# BQ51013BSCH.net
KiCad netlist of a schematic drawn in Altium Designer
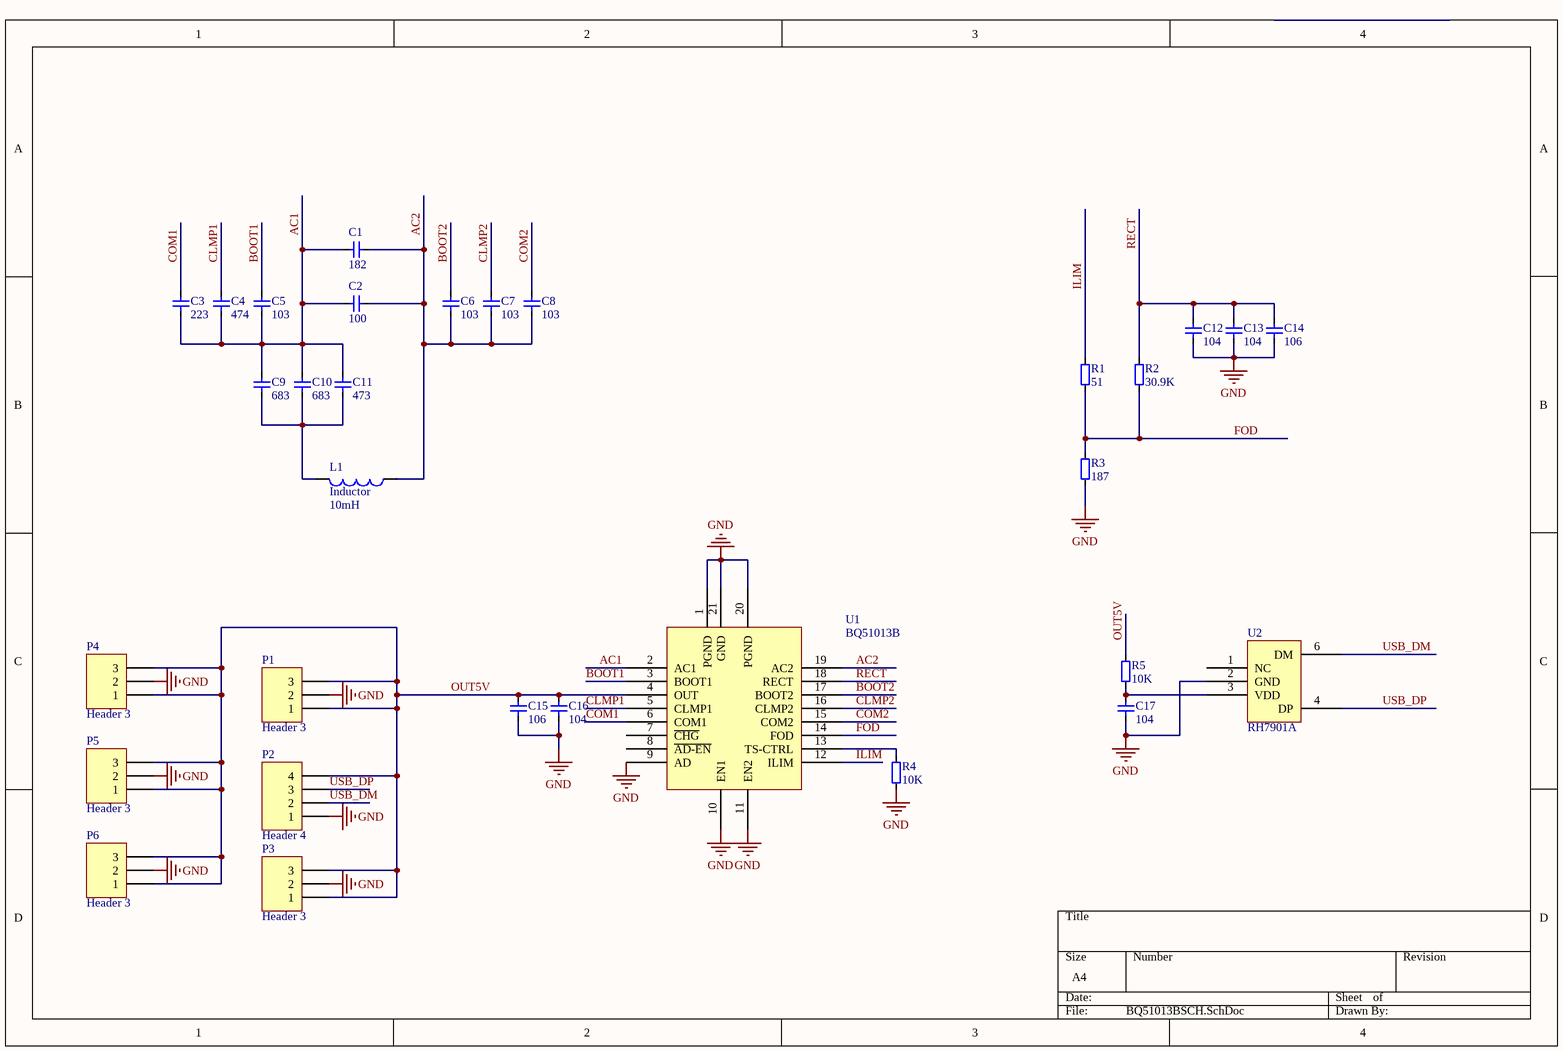
[diagram p0: BQ51013BSCH.SchDoc]

(export (version "E")
  (design (tool "Eeschema 10.0.6"))
  (components
    (comp (ref "C1")
      (value "182")
      (footprint "RECTANGLE/5.5/7.5/2.5")
      (description "Capacitor")
      (libsource (lib "5V1A1.1") (part "CAP1"))
    )
    (comp (ref "C2")
      (value "100")
      (footprint "RECTANGLE/5.5/7.5/2.5")
      (description "Capacitor")
      (libsource (lib "WP8AA0") (part "CAP1"))
    )
    (comp (ref "C3") (value "223") (description "Capacitor") (libsource (lib "5V1A1.1") (part "CAP1")))
    (comp (ref "C4")
      (value "474")
      (footprint "RECTANGLE/5.5/7.5/2.5")
      (description "Capacitor")
      (libsource (lib "5V1A1.1") (part "CAP1"))
    )
    (comp (ref "C5")
      (value "103")
      (footprint "RECTANGLE/5.5/7.5/2.5")
      (description "Capacitor")
      (libsource (lib "5V1A1.1") (part "CAP1"))
    )
    (comp (ref "C6")
      (value "103")
      (footprint "RECTANGLE/5.5/7.5/2.5")
      (description "Capacitor")
      (libsource (lib "5V1A1.1") (part "CAP1"))
    )
    (comp (ref "C7")
      (value "103")
      (footprint "RECTANGLE/5.5/7.5/2.5")
      (description "Capacitor")
      (libsource (lib "5V1A1.1") (part "CAP1"))
    )
    (comp (ref "C8")
      (value "103")
      (footprint "RECTANGLE/5.5/7.5/2.5")
      (description "Capacitor")
      (libsource (lib "5V1A1.1") (part "CAP1"))
    )
    (comp (ref "C9")
      (value "683")
      (footprint "RECTANGLE/5.5/7.5/2.5")
      (description "Capacitor")
      (libsource (lib "5V1A1.1") (part "CAP1"))
    )
    (comp (ref "C10")
      (value "683")
      (footprint "RECTANGLE/5.5/7.5/2.5")
      (description "Capacitor")
      (libsource (lib "5V1A1.1") (part "CAP1"))
    )
    (comp (ref "C11")
      (value "473")
      (footprint "RECTANGLE/5.5/7.5/2.5")
      (description "Capacitor")
      (libsource (lib "5V1A1.1") (part "CAP1"))
    )
    (comp (ref "C12")
      (value "104")
      (footprint "RECTANGLE/5.5/7.5/2.5")
      (description "Capacitor")
      (libsource (lib "5V1A1.1") (part "CAP1"))
    )
    (comp (ref "C13")
      (value "104")
      (footprint "RECTANGLE/5.5/7.5/2.5")
      (description "Capacitor")
      (libsource (lib "5V1A1.1") (part "CAP1"))
    )
    (comp (ref "C14")
      (value "106")
      (footprint "RECTANGLE/5.5/7.5/2.5")
      (description "Capacitor")
      (libsource (lib "5V1A1.1") (part "CAP1"))
    )
    (comp (ref "C15")
      (value "106")
      (footprint "RECTANGLE/5.5/7.5/2.5")
      (description "Capacitor")
      (libsource (lib "5V1A1.1") (part "CAP1"))
    )
    (comp (ref "C16")
      (value "104")
      (footprint "RECTANGLE/5.5/7.5/2.5")
      (description "Capacitor")
      (libsource (lib "5V1A1.1") (part "CAP1"))
    )
    (comp (ref "C17")
      (value "104")
      (footprint "RECTANGLE/5.5/7.5/2.5")
      (description "Capacitor")
      (libsource (lib "5V1A1.1") (part "CAP1"))
    )
    (comp (ref "L1")
      (value "Inductor")
      (footprint "5V1AV1.1:5vinc")
      (fields (field (name "ALTIUM_VALUE") "10mH") (field (name "PUBLISHER") "Altium Limited"))
      (libsource (lib "Miscellaneous Devices") (part "Inductor"))
    )
    (comp (ref "P1")
      (value "Header 3")
      (footprint "5V1AV1.1:RXConnect")
      (description "Header, 3-Pin")
      (fields (field (name "PUBLISHER") "Altium Limited"))
      (libsource (lib "Miscellaneous Connectors") (part "Header 3"))
    )
    (comp (ref "P2")
      (value "Header 4")
      (footprint "5V1AV1.1:USB_CONNECT")
      (description "Header, 4-Pin")
      (fields (field (name "PUBLISHER") "Altium Limited"))
      (libsource (lib "Miscellaneous Connectors") (part "Header 4"))
    )
    (comp (ref "P3")
      (value "Header 3")
      (footprint "5V1AV1.1:RXConnect")
      (description "Header, 3-Pin")
      (fields (field (name "PUBLISHER") "Altium Limited"))
      (libsource (lib "Miscellaneous Connectors") (part "Header 3"))
    )
    (comp (ref "P4")
      (value "Header 3")
      (footprint "5V1AV1.1:RXConnect")
      (description "Header, 3-Pin")
      (fields (field (name "PUBLISHER") "Altium Limited"))
      (libsource (lib "Miscellaneous Connectors") (part "Header 3"))
    )
    (comp (ref "P5")
      (value "Header 3")
      (footprint "5V1AV1.1:RXConnect")
      (description "Header, 3-Pin")
      (fields (field (name "PUBLISHER") "Altium Limited"))
      (libsource (lib "Miscellaneous Connectors") (part "Header 3"))
    )
    (comp (ref "P6")
      (value "Header 3")
      (footprint "5V1AV1.1:RXConnect")
      (description "Header, 3-Pin")
      (fields (field (name "PUBLISHER") "Altium Limited"))
      (libsource (lib "Miscellaneous Connectors") (part "Header 3"))
    )
    (comp (ref "R1")
      (value "51")
      (footprint "R12.5/2.5")
      (description "电阻")
      (libsource (lib "5V1A1.1") (part "RES6"))
    )
    (comp (ref "R2")
      (value "30.9K")
      (footprint "R12.5/2.5")
      (description "电阻")
      (libsource (lib "5V1A1.1") (part "RES6"))
    )
    (comp (ref "R3")
      (value "187")
      (footprint "R12.5/2.5")
      (description "电阻")
      (libsource (lib "5V1A1.1") (part "RES6"))
    )
    (comp (ref "R4")
      (value "10K")
      (footprint "R12.5/2.5")
      (description "电阻")
      (libsource (lib "5V1A1.1") (part "RES6"))
    )
    (comp (ref "R5") (value "10K") (description "电阻") (libsource (lib "5V1A1.1") (part "RES6")))
    (comp (ref "U1") (value "BQ51013B") (footprint "PVQFN-N20") (libsource (lib "5V1A1.1") (part "BQ51013B")))
    (comp (ref "U2")
      (value "RH7901A")
      (footprint "SOT23-6_L")
      (description "RH7019A")
      (libsource (lib "5V1A1.1") (part "RH7901A"))
    )
  )
  (nets
    (net (code "1") (name "/AC1") (class "Default")
      (node (ref "C1") (pin "1") (pinfunction "1_1") (pintype "passive"))
      (node (ref "C10") (pin "1") (pinfunction "1_1") (pintype "passive"))
      (node (ref "C11") (pin "1") (pinfunction "1_1") (pintype "passive"))
      (node (ref "C2") (pin "1") (pinfunction "1_1") (pintype "passive"))
      (node (ref "C3") (pin "2") (pinfunction "2_2") (pintype "passive"))
      (node (ref "C4") (pin "2") (pinfunction "2_2") (pintype "passive"))
      (node (ref "C5") (pin "2") (pinfunction "2_2") (pintype "passive"))
      (node (ref "C9") (pin "1") (pinfunction "1_1") (pintype "passive"))
      (node (ref "U1") (pin "2") (pinfunction "AC1_2") (pintype "passive"))
    )
    (net (code "2") (name "/AC2") (class "Default")
      (node (ref "C1") (pin "2") (pinfunction "2_2") (pintype "passive"))
      (node (ref "C2") (pin "2") (pinfunction "2_2") (pintype "passive"))
      (node (ref "C6") (pin "2") (pinfunction "2_2") (pintype "passive"))
      (node (ref "C7") (pin "2") (pinfunction "2_2") (pintype "passive"))
      (node (ref "C8") (pin "2") (pinfunction "2_2") (pintype "passive"))
      (node (ref "L1") (pin "1") (pinfunction "1_1") (pintype "passive"))
      (node (ref "U1") (pin "19") (pinfunction "AC2_19") (pintype "passive"))
    )
    (net (code "3") (name "/BOOT1") (class "Default")
      (node (ref "C5") (pin "1") (pinfunction "1_1") (pintype "passive"))
      (node (ref "U1") (pin "3") (pinfunction "BOOT1_3") (pintype "passive"))
    )
    (net (code "4") (name "/BOOT2") (class "Default")
      (node (ref "C6") (pin "1") (pinfunction "1_1") (pintype "passive"))
      (node (ref "U1") (pin "17") (pinfunction "BOOT2_17") (pintype "passive"))
    )
    (net (code "5") (name "/CLMP1") (class "Default")
      (node (ref "C4") (pin "1") (pinfunction "1_1") (pintype "passive"))
      (node (ref "U1") (pin "5") (pinfunction "CLMP1_5") (pintype "passive"))
    )
    (net (code "6") (name "/CLMP2") (class "Default")
      (node (ref "C7") (pin "1") (pinfunction "1_1") (pintype "passive"))
      (node (ref "U1") (pin "16") (pinfunction "CLMP2_16") (pintype "passive"))
    )
    (net (code "7") (name "/COM1") (class "Default")
      (node (ref "C3") (pin "1") (pinfunction "1_1") (pintype "passive"))
      (node (ref "U1") (pin "6") (pinfunction "COM1_6") (pintype "passive"))
    )
    (net (code "8") (name "/COM2") (class "Default")
      (node (ref "C8") (pin "1") (pinfunction "1_1") (pintype "passive"))
      (node (ref "U1") (pin "15") (pinfunction "COM2_15") (pintype "passive"))
    )
    (net (code "9") (name "/FOD") (class "Default")
      (node (ref "R1") (pin "1") (pinfunction "1_1") (pintype "passive"))
      (node (ref "R2") (pin "1") (pinfunction "1_1") (pintype "passive"))
      (node (ref "R3") (pin "2") (pinfunction "2_2") (pintype "passive"))
      (node (ref "U1") (pin "14") (pinfunction "FOD_14") (pintype "passive"))
    )
    (net (code "10") (name "/ILIM") (class "Default")
      (node (ref "R1") (pin "2") (pinfunction "2_2") (pintype "passive"))
      (node (ref "U1") (pin "12") (pinfunction "ILIM_12") (pintype "passive"))
    )
    (net (code "11") (name "/OUT5V") (class "Default")
      (node (ref "C15") (pin "1") (pinfunction "1_1") (pintype "passive"))
      (node (ref "C16") (pin "1") (pinfunction "1_1") (pintype "passive"))
      (node (ref "P1") (pin "1") (pinfunction "1_1") (pintype "passive"))
      (node (ref "P1") (pin "3") (pinfunction "3_3") (pintype "passive"))
      (node (ref "P2") (pin "4") (pinfunction "4_4") (pintype "passive"))
      (node (ref "P3") (pin "1") (pinfunction "1_1") (pintype "passive"))
      (node (ref "P3") (pin "3") (pinfunction "3_3") (pintype "passive"))
      (node (ref "P4") (pin "1") (pinfunction "1_1") (pintype "passive"))
      (node (ref "P4") (pin "3") (pinfunction "3_3") (pintype "passive"))
      (node (ref "P5") (pin "1") (pinfunction "1_1") (pintype "passive"))
      (node (ref "P5") (pin "3") (pinfunction "3_3") (pintype "passive"))
      (node (ref "P6") (pin "1") (pinfunction "1_1") (pintype "passive"))
      (node (ref "P6") (pin "3") (pinfunction "3_3") (pintype "passive"))
      (node (ref "R5") (pin "2") (pinfunction "2_2") (pintype "passive"))
      (node (ref "U1") (pin "4") (pinfunction "OUT_4") (pintype "passive"))
    )
    (net (code "12") (name "/RECT") (class "Default")
      (node (ref "C12") (pin "2") (pinfunction "2_2") (pintype "passive"))
      (node (ref "C13") (pin "2") (pinfunction "2_2") (pintype "passive"))
      (node (ref "C14") (pin "2") (pinfunction "2_2") (pintype "passive"))
      (node (ref "R2") (pin "2") (pinfunction "2_2") (pintype "passive"))
      (node (ref "U1") (pin "18") (pinfunction "RECT_18") (pintype "passive"))
    )
    (net (code "13") (name "/USB_DM") (class "Default")
      (node (ref "P2") (pin "2") (pinfunction "2_2") (pintype "passive"))
      (node (ref "U2") (pin "6") (pinfunction "DM_6") (pintype "passive"))
    )
    (net (code "14") (name "/USB_DP") (class "Default")
      (node (ref "P2") (pin "3") (pinfunction "3_3") (pintype "passive"))
      (node (ref "U2") (pin "4") (pinfunction "DP_4") (pintype "passive"))
    )
    (net (code "15") (name "GND") (class "Default")
      (node (ref "C12") (pin "1") (pinfunction "1_1") (pintype "passive"))
      (node (ref "C13") (pin "1") (pinfunction "1_1") (pintype "passive"))
      (node (ref "C14") (pin "1") (pinfunction "1_1") (pintype "passive"))
      (node (ref "C15") (pin "2") (pinfunction "2_2") (pintype "passive"))
      (node (ref "C16") (pin "2") (pinfunction "2_2") (pintype "passive"))
      (node (ref "C17") (pin "1") (pinfunction "1_1") (pintype "passive"))
      (node (ref "P1") (pin "2") (pinfunction "2_2") (pintype "passive"))
      (node (ref "P2") (pin "1") (pinfunction "1_1") (pintype "passive"))
      (node (ref "P3") (pin "2") (pinfunction "2_2") (pintype "passive"))
      (node (ref "P4") (pin "2") (pinfunction "2_2") (pintype "passive"))
      (node (ref "P5") (pin "2") (pinfunction "2_2") (pintype "passive"))
      (node (ref "P6") (pin "2") (pinfunction "2_2") (pintype "passive"))
      (node (ref "R3") (pin "1") (pinfunction "1_1") (pintype "passive"))
      (node (ref "R4") (pin "1") (pinfunction "1_1") (pintype "passive"))
      (node (ref "U1") (pin "1") (pinfunction "PGND_1") (pintype "passive"))
      (node (ref "U1") (pin "10") (pinfunction "EN1_10") (pintype "passive"))
      (node (ref "U1") (pin "11") (pinfunction "EN2_11") (pintype "passive"))
      (node (ref "U1") (pin "20") (pinfunction "PGND_20") (pintype "passive"))
      (node (ref "U1") (pin "21") (pinfunction "GND_21") (pintype "passive"))
      (node (ref "U1") (pin "9") (pinfunction "AD_9") (pintype "passive"))
      (node (ref "U2") (pin "2") (pinfunction "GND_2") (pintype "passive"))
    )
    (net (code "16") (name "Net-(C10-Pad2)") (class "Default")
      (node (ref "C10") (pin "2") (pinfunction "2_2") (pintype "passive"))
      (node (ref "C11") (pin "2") (pinfunction "2_2") (pintype "passive"))
      (node (ref "C9") (pin "2") (pinfunction "2_2") (pintype "passive"))
      (node (ref "L1") (pin "2") (pinfunction "2_2") (pintype "passive"))
    )
    (net (code "17") (name "Net-(U1-TS-CTRL)") (class "Default")
      (node (ref "R4") (pin "2") (pinfunction "2_2") (pintype "passive"))
      (node (ref "U1") (pin "13") (pinfunction "TS-CTRL_13") (pintype "passive"))
    )
    (net (code "18") (name "Net-(U2-VDD)") (class "Default")
      (node (ref "C17") (pin "2") (pinfunction "2_2") (pintype "passive"))
      (node (ref "R5") (pin "1") (pinfunction "1_1") (pintype "passive"))
      (node (ref "U2") (pin "3") (pinfunction "VDD_3") (pintype "passive"))
    )
    (net (code "19") (name "unconnected-(U1-~{AD-EN}-Pad8)") (class "Default")
      (node (ref "U1") (pin "8") (pinfunction "~{AD-EN}_8") (pintype "passive"))
    )
    (net (code "20") (name "unconnected-(U1-~{CHG}-Pad7)") (class "Default")
      (node (ref "U1") (pin "7") (pinfunction "~{CHG}_7") (pintype "passive"))
    )
    (net (code "21") (name "unconnected-(U2-NC-Pad1)") (class "Default")
      (node (ref "U2") (pin "1") (pinfunction "NC_1") (pintype "passive"))
    )
  )
)
